# db9nes.net
KiCad netlist of a schematic drawn in EAGLE
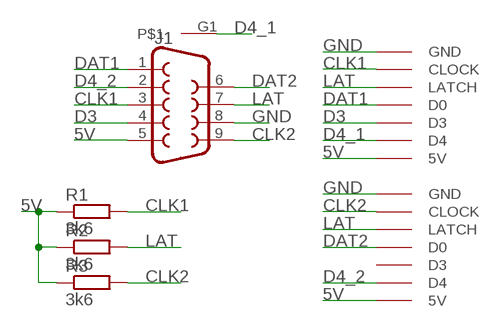
[diagram p0: schematic, sheet 1]

(export (version "E")
  (design (tool "Eeschema 10.0.6"))
  (components
    (comp (ref "J1")
      (value "DB9FEMALE")
      (footprint "eagle-import:DB9")
      (libsource (lib "eagle-import") (part "DB9FEMALE"))
    )
    (comp (ref "R1")
      (value "3k6")
      (footprint "eagle-import:R0603")
      (libsource (lib "eagle-import") (part "R-EU_R0603"))
    )
    (comp (ref "R2")
      (value "3k6")
      (footprint "eagle-import:R0603")
      (libsource (lib "eagle-import") (part "R-EU_R0603"))
    )
    (comp (ref "R3")
      (value "3k6")
      (footprint "eagle-import:R0603")
      (libsource (lib "eagle-import") (part "R-EU_R0603"))
    )
    (comp (ref "U$1")
      (value "NESCONNNO_TABS")
      (footprint "eagle-import:NESCONN_NO_TABS")
      (libsource (lib "eagle-import") (part "NESCONNNO_TABS"))
    )
    (comp (ref "U$2")
      (value "NESCONNNO_TABS")
      (footprint "eagle-import:NESCONN_NO_TABS")
      (libsource (lib "eagle-import") (part "NESCONNNO_TABS"))
    )
  )
  (nets
    (net (code "1") (name "/5V") (class "Default")
      (node (ref "J1") (pin "5") (pinfunction "5_5") (pintype "passive"))
      (node (ref "R1") (pin "1") (pinfunction "1_1") (pintype "passive"))
      (node (ref "R2") (pin "1") (pinfunction "1_1") (pintype "passive"))
      (node (ref "R3") (pin "1") (pinfunction "1_1") (pintype "passive"))
      (node (ref "U$1") (pin "5V") (pinfunction "5V_5V") (pintype "power_in"))
      (node (ref "U$2") (pin "5V") (pinfunction "5V_5V") (pintype "power_in"))
    )
    (net (code "2") (name "/CLK1") (class "Default")
      (node (ref "J1") (pin "3") (pinfunction "3_3") (pintype "passive"))
      (node (ref "R1") (pin "2") (pinfunction "2_2") (pintype "passive"))
      (node (ref "U$2") (pin "CLOCK") (pinfunction "CLOCK_CLOCK") (pintype "input"))
    )
    (net (code "3") (name "/CLK2") (class "Default")
      (node (ref "J1") (pin "9") (pinfunction "9_9") (pintype "passive"))
      (node (ref "R3") (pin "2") (pinfunction "2_2") (pintype "passive"))
      (node (ref "U$1") (pin "CLOCK") (pinfunction "CLOCK_CLOCK") (pintype "input"))
    )
    (net (code "4") (name "/D3") (class "Default")
      (node (ref "J1") (pin "4") (pinfunction "4_4") (pintype "passive"))
      (node (ref "U$2") (pin "D3") (pinfunction "D3_D3") (pintype "bidirectional"))
    )
    (net (code "5") (name "/D4_1") (class "Default")
      (node (ref "J1") (pin "G1") (pinfunction "P$1_G1") (pintype "bidirectional"))
      (node (ref "U$2") (pin "D4") (pinfunction "D4_D4") (pintype "bidirectional"))
    )
    (net (code "6") (name "/D4_2") (class "Default")
      (node (ref "J1") (pin "2") (pinfunction "2_2") (pintype "passive"))
      (node (ref "U$1") (pin "D4") (pinfunction "D4_D4") (pintype "bidirectional"))
    )
    (net (code "7") (name "/DAT1") (class "Default")
      (node (ref "J1") (pin "1") (pinfunction "1_1") (pintype "passive"))
      (node (ref "U$2") (pin "D0") (pinfunction "D0_D0") (pintype "bidirectional"))
    )
    (net (code "8") (name "/DAT2") (class "Default")
      (node (ref "J1") (pin "6") (pinfunction "6_6") (pintype "passive"))
      (node (ref "U$1") (pin "D0") (pinfunction "D0_D0") (pintype "bidirectional"))
    )
    (net (code "9") (name "/GND") (class "Default")
      (node (ref "J1") (pin "8") (pinfunction "8_8") (pintype "passive"))
      (node (ref "U$1") (pin "GND") (pinfunction "GND_GND") (pintype "input"))
      (node (ref "U$2") (pin "GND") (pinfunction "GND_GND") (pintype "input"))
    )
    (net (code "10") (name "/LAT") (class "Default")
      (node (ref "J1") (pin "7") (pinfunction "7_7") (pintype "passive"))
      (node (ref "R2") (pin "2") (pinfunction "2_2") (pintype "passive"))
      (node (ref "U$1") (pin "LATCH") (pinfunction "LATCH_LATCH") (pintype "input"))
      (node (ref "U$2") (pin "LATCH") (pinfunction "LATCH_LATCH") (pintype "input"))
    )
    (net (code "11") (name "unconnected-(U$1-PadD3)") (class "Default")
      (node (ref "U$1") (pin "D3") (pinfunction "D3_D3") (pintype "bidirectional"))
    )
  )
)
